# 1-Schematic_EMWAVER_V1_0_1.net
KiCad netlist of a schematic drawn in EasyEDA
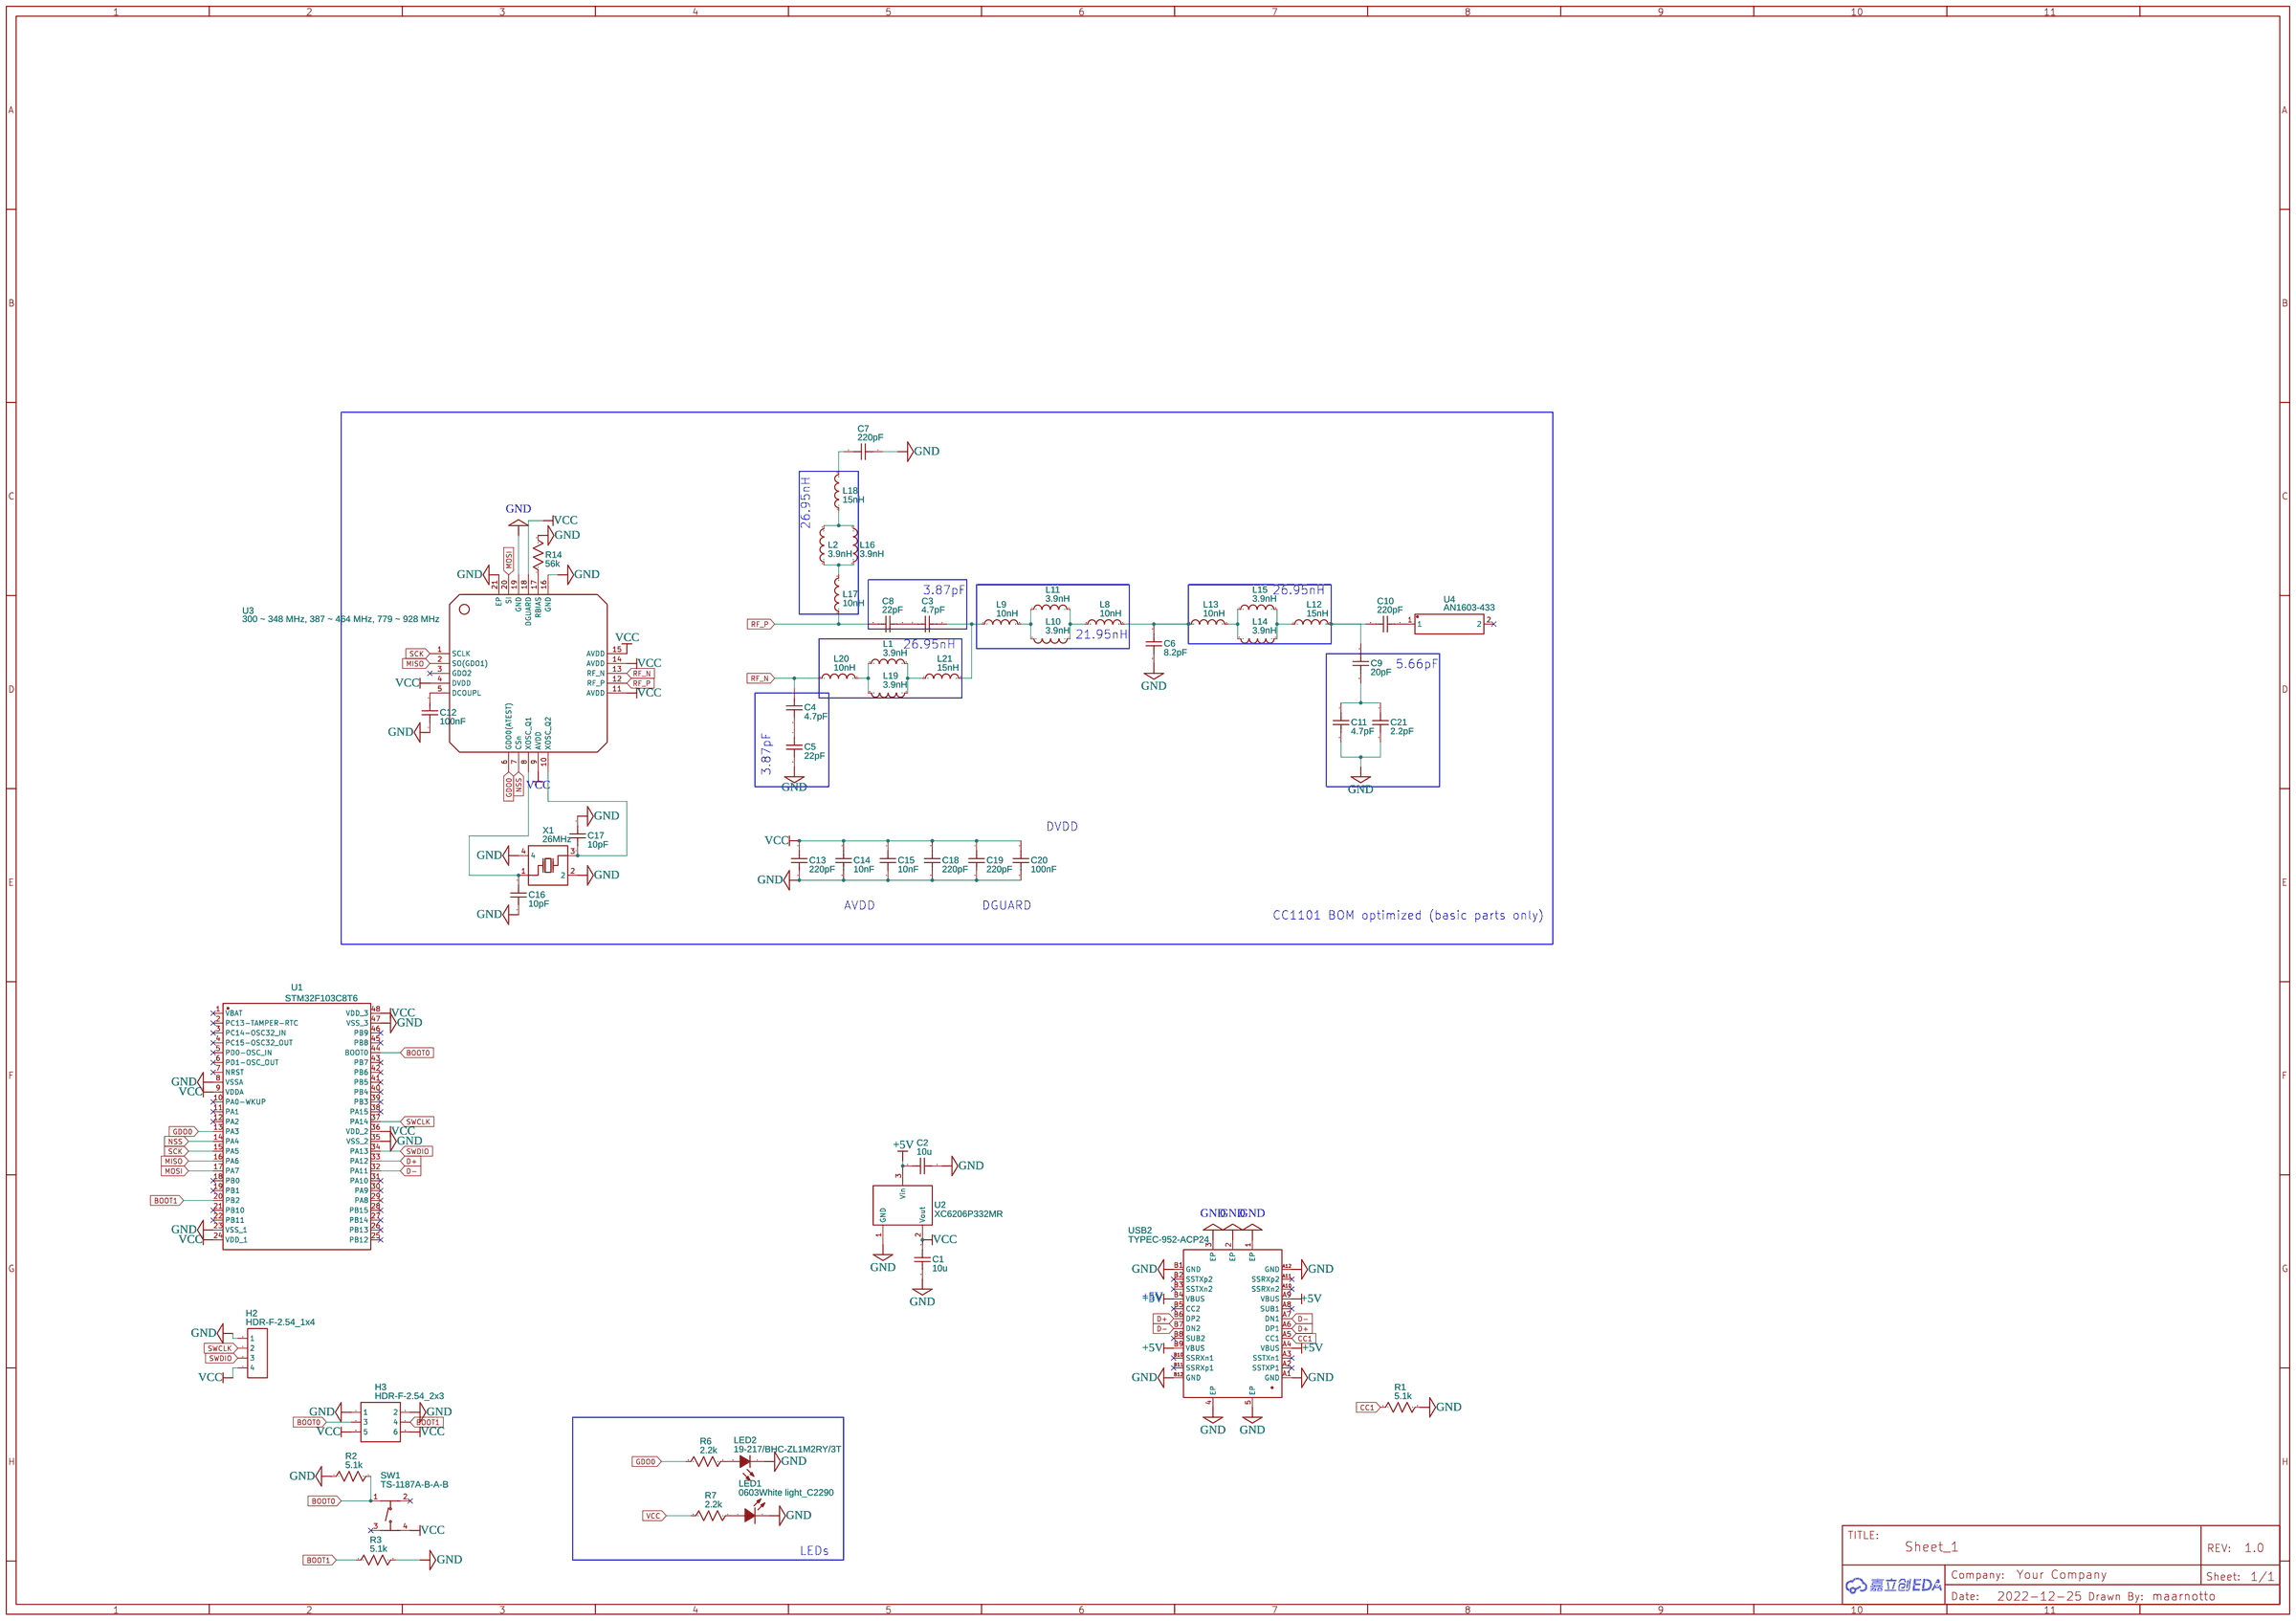
[diagram p0: schematic sheet]

(export (version "E")
  (design (tool "Eeschema 10.0.6"))
  (components
    (comp (ref "C1") (value "10u") (libsource (lib "") (part "C_0603_US_1")))
    (comp (ref "C2") (value "10u") (libsource (lib "") (part "C_0603_US")))
    (comp (ref "C3") (value "4.7pF") (libsource (lib "") (part "C_0402_US_1")))
    (comp (ref "C4") (value "4.7pF") (libsource (lib "") (part "C_0402_US")))
    (comp (ref "C5") (value "22pF") (libsource (lib "") (part "C_0402_US")))
    (comp (ref "C6") (value "8.2pF") (libsource (lib "") (part "C_0603_US_1")))
    (comp (ref "C7") (value "220pF") (libsource (lib "") (part "C_0402_US_1")))
    (comp (ref "C8") (value "22pF") (libsource (lib "") (part "C_0402_US_1")))
    (comp (ref "C9") (value "20pF") (libsource (lib "") (part "C_0402_US")))
    (comp (ref "C10") (value "220pF") (libsource (lib "") (part "C_0402_US_1")))
    (comp (ref "C11") (value "4.7pF") (libsource (lib "") (part "C_0402_US")))
    (comp (ref "C12") (value "100nF") (libsource (lib "") (part "C_0402_US")))
    (comp (ref "C13") (value "220pF") (libsource (lib "") (part "C_0402_US")))
    (comp (ref "C14") (value "10nF") (libsource (lib "") (part "C_0402_US")))
    (comp (ref "C15") (value "10nF") (libsource (lib "") (part "C_0402_US")))
    (comp (ref "C16") (value "10pF") (libsource (lib "") (part "C_0402_US")))
    (comp (ref "C17") (value "10pF") (libsource (lib "") (part "C_0402_US_2")))
    (comp (ref "C18") (value "220pF") (libsource (lib "") (part "C_0402_US")))
    (comp (ref "C19") (value "220pF") (libsource (lib "") (part "C_0402_US")))
    (comp (ref "C20") (value "100nF") (libsource (lib "") (part "C_0402_US")))
    (comp (ref "C21") (value "2.2pF") (libsource (lib "") (part "C_0402_US")))
    (comp (ref "H2")
      (value "HDR-F-2.54_1x4")
      (fields (field (name "BOM_Supplier Part") "C225501"))
      (libsource (lib "") (part "HDR-F-2.54_1x4"))
    )
    (comp (ref "H3")
      (value "HDR-F-2.54_2x3")
      (fields (field (name "BOM_Supplier Part") "C65114"))
      (libsource (lib "") (part "HDR-F-2.54_2x3"))
    )
    (comp (ref "L1")
      (value "3.9nH")
      (fields (field (name "BOM_Supplier Part") "C14033"))
      (libsource (lib "") (part "L0402_US_1"))
    )
    (comp (ref "L2")
      (value "3.9nH")
      (fields (field (name "BOM_Supplier Part") "C14033"))
      (libsource (lib "") (part "L0402_US_3"))
    )
    (comp (ref "L8")
      (value "10nH")
      (fields (field (name "BOM_Supplier Part") "C27147"))
      (libsource (lib "") (part "L0402_US"))
    )
    (comp (ref "L9")
      (value "10nH")
      (fields (field (name "BOM_Supplier Part") "C27147"))
      (libsource (lib "") (part "L0402_US_1"))
    )
    (comp (ref "L10")
      (value "3.9nH")
      (fields (field (name "BOM_Supplier Part") "C14033"))
      (libsource (lib "") (part "L0402_US_4"))
    )
    (comp (ref "L11")
      (value "3.9nH")
      (fields (field (name "BOM_Supplier Part") "C14033"))
      (libsource (lib "") (part "L0402_US"))
    )
    (comp (ref "L12")
      (value "15nH")
      (fields (field (name "BOM_Supplier Part") "C27143"))
      (libsource (lib "") (part "L0402_US"))
    )
    (comp (ref "L13")
      (value "10nH")
      (fields (field (name "BOM_Supplier Part") "C27147"))
      (libsource (lib "") (part "L0402_US"))
    )
    (comp (ref "L14")
      (value "3.9nH")
      (fields (field (name "BOM_Supplier Part") "C14033"))
      (libsource (lib "") (part "L0402_US_4"))
    )
    (comp (ref "L15")
      (value "3.9nH")
      (fields (field (name "BOM_Supplier Part") "C14033"))
      (libsource (lib "") (part "L0402_US"))
    )
    (comp (ref "L16")
      (value "3.9nH")
      (fields (field (name "BOM_Supplier Part") "C14033"))
      (libsource (lib "") (part "L0402_US_2"))
    )
    (comp (ref "L17")
      (value "10nH")
      (fields (field (name "BOM_Supplier Part") "C27147"))
      (libsource (lib "") (part "L0402_US_3"))
    )
    (comp (ref "L18")
      (value "15nH")
      (fields (field (name "BOM_Supplier Part") "C27143"))
      (libsource (lib "") (part "L0402_US_3"))
    )
    (comp (ref "L19")
      (value "3.9nH")
      (fields (field (name "BOM_Supplier Part") "C14033"))
      (libsource (lib "") (part "L0402_US_5"))
    )
    (comp (ref "L20")
      (value "10nH")
      (fields (field (name "BOM_Supplier Part") "C27147"))
      (libsource (lib "") (part "L0402_US_1"))
    )
    (comp (ref "L21")
      (value "15nH")
      (fields (field (name "BOM_Supplier Part") "C27143"))
      (libsource (lib "") (part "L0402_US_1"))
    )
    (comp (ref "LED1")
      (value "0603White light_C2290")
      (fields (field (name "BOM_Manufacturer Part") "KT-0603白灯") (field (name "BOM_Supplier Part") "C2290"))
      (libsource (lib "") (part "0603White light_C2290"))
    )
    (comp (ref "LED2")
      (value "19-217/BHC-ZL1M2RY/3T")
      (fields (field (name "BOM_Supplier Part") "C72041"))
      (libsource (lib "") (part "19-217/BHC-ZL1M2RY/3T"))
    )
    (comp (ref "R1") (value "5.1k") (libsource (lib "") (part "R_0603_US")))
    (comp (ref "R2") (value "5.1k") (libsource (lib "") (part "R_0603_US")))
    (comp (ref "R3") (value "5.1k") (libsource (lib "") (part "R_0603_US")))
    (comp (ref "R6") (value "2.2k") (libsource (lib "") (part "R_0603_US")))
    (comp (ref "R7") (value "2.2k") (libsource (lib "") (part "R_0603_US")))
    (comp (ref "R14") (value "56k") (libsource (lib "") (part "R_0402_US")))
    (comp (ref "SW1")
      (value "TS-1187A-B-A-B")
      (fields (field (name "BOM_Supplier Part") "C318884"))
      (libsource (lib "") (part "TS-1187A-B-A-B"))
    )
    (comp (ref "U1")
      (value "STM32F103C8T6")
      (fields (field (name "BOM_Supplier Part") "C8734"))
      (libsource (lib "") (part "STM32F103C8T6"))
    )
    (comp (ref "U2")
      (value "XC6206P332MR")
      (fields (field (name "BOM_Supplier Part") "C5446"))
      (libsource (lib "") (part "XC6206P332MR"))
    )
    (comp (ref "U3")
      (value "300 ~ 348 MHz, 387 ~ 464 MHz, 779 ~ 928 MHz")
      (fields (field (name "BOM_Manufacturer Part") "CC1101RGPR") (field (name "BOM_Supplier Part") "C29953"))
      (libsource (lib "") (part "CC1101RGPR"))
    )
    (comp (ref "U4")
      (value "AN1603-433")
      (fields (field (name "BOM_Supplier Part") "C122806"))
      (libsource (lib "") (part "AN1603-433"))
    )
    (comp (ref "USB2")
      (value "TYPEC-952-ACP24")
      (fields (field (name "BOM_Supplier Part") "C2840398"))
      (libsource (lib "") (part "TYPEC-952-ACP24"))
    )
    (comp (ref "X1")
      (value "26MHz")
      (fields
        (field (name "BOM_Manufacturer Part") "3S26000333")
        (field (name "BOM_Supplier Part") "C431163")
      )
      (libsource (lib "") (part "3S26000333"))
    )
  )
  (nets
    (net (code "1") (name "+5V") (class "Default")
      (node (ref "C2") (pin "2") (pinfunction "2_2") (pintype "unspecified"))
      (node (ref "U2") (pin "3") (pinfunction "Vin_3") (pintype "unspecified"))
      (node (ref "USB2") (pin "A4") (pinfunction "VBUS_A4") (pintype "unspecified"))
      (node (ref "USB2") (pin "A9") (pinfunction "VBUS_A9") (pintype "unspecified"))
      (node (ref "USB2") (pin "B4") (pinfunction "VBUS_B4") (pintype "unspecified"))
      (node (ref "USB2") (pin "B9") (pinfunction "VBUS_B9") (pintype "unspecified"))
    )
    (net (code "2") (name "BOOT0") (class "Default")
      (node (ref "H3") (pin "3") (pinfunction "3_3") (pintype "input"))
      (node (ref "R2") (pin "2") (pinfunction "2_2") (pintype "unspecified"))
      (node (ref "SW1") (pin "1") (pinfunction "A_1") (pintype "unspecified"))
      (node (ref "U1") (pin "44") (pinfunction "BOOT0_44") (pintype "unspecified"))
    )
    (net (code "3") (name "BOOT1") (class "Default")
      (node (ref "H3") (pin "4") (pinfunction "4_4") (pintype "input"))
      (node (ref "R3") (pin "1") (pinfunction "1_1") (pintype "unspecified"))
      (node (ref "U1") (pin "20") (pinfunction "PB2_20") (pintype "unspecified"))
    )
    (net (code "4") (name "CC1") (class "Default")
      (node (ref "R1") (pin "1") (pinfunction "1_1") (pintype "unspecified"))
      (node (ref "USB2") (pin "A5") (pinfunction "CC1_A5") (pintype "unspecified"))
    )
    (net (code "5") (name "D+") (class "Default")
      (node (ref "U1") (pin "33") (pinfunction "PA12_33") (pintype "unspecified"))
      (node (ref "USB2") (pin "A6") (pinfunction "DP1_A6") (pintype "unspecified"))
      (node (ref "USB2") (pin "B6") (pinfunction "DP2_B6") (pintype "unspecified"))
    )
    (net (code "6") (name "D-") (class "Default")
      (node (ref "U1") (pin "32") (pinfunction "PA11_32") (pintype "unspecified"))
      (node (ref "USB2") (pin "A7") (pinfunction "DN1_A7") (pintype "unspecified"))
      (node (ref "USB2") (pin "B7") (pinfunction "DN2_B7") (pintype "unspecified"))
    )
    (net (code "7") (name "GDO0") (class "Default")
      (node (ref "R6") (pin "1") (pinfunction "1_1") (pintype "unspecified"))
      (node (ref "U1") (pin "13") (pinfunction "PA3_13") (pintype "unspecified"))
      (node (ref "U3") (pin "6") (pinfunction "GDO0(ATEST)_6") (pintype "unspecified"))
    )
    (net (code "8") (name "GND") (class "Default")
      (node (ref "C1") (pin "2") (pinfunction "2_2") (pintype "unspecified"))
      (node (ref "C11") (pin "2") (pinfunction "2_2") (pintype "unspecified"))
      (node (ref "C12") (pin "2") (pinfunction "2_2") (pintype "unspecified"))
      (node (ref "C13") (pin "2") (pinfunction "2_2") (pintype "unspecified"))
      (node (ref "C14") (pin "2") (pinfunction "2_2") (pintype "unspecified"))
      (node (ref "C15") (pin "2") (pinfunction "2_2") (pintype "unspecified"))
      (node (ref "C16") (pin "2") (pinfunction "2_2") (pintype "unspecified"))
      (node (ref "C17") (pin "2") (pinfunction "2_2") (pintype "unspecified"))
      (node (ref "C18") (pin "2") (pinfunction "2_2") (pintype "unspecified"))
      (node (ref "C19") (pin "2") (pinfunction "2_2") (pintype "unspecified"))
      (node (ref "C2") (pin "1") (pinfunction "1_1") (pintype "unspecified"))
      (node (ref "C20") (pin "2") (pinfunction "2_2") (pintype "unspecified"))
      (node (ref "C21") (pin "2") (pinfunction "2_2") (pintype "unspecified"))
      (node (ref "C5") (pin "2") (pinfunction "2_2") (pintype "unspecified"))
      (node (ref "C6") (pin "2") (pinfunction "2_2") (pintype "unspecified"))
      (node (ref "C7") (pin "1") (pinfunction "1_1") (pintype "unspecified"))
      (node (ref "H2") (pin "1") (pinfunction "1_1") (pintype "unspecified"))
      (node (ref "H3") (pin "1") (pinfunction "1_1") (pintype "input"))
      (node (ref "H3") (pin "2") (pinfunction "2_2") (pintype "input"))
      (node (ref "LED1") (pin "2") (pinfunction "K_2") (pintype "unspecified"))
      (node (ref "LED2") (pin "1") (pinfunction "C_1") (pintype "input"))
      (node (ref "R1") (pin "2") (pinfunction "2_2") (pintype "unspecified"))
      (node (ref "R14") (pin "2") (pinfunction "2_2") (pintype "unspecified"))
      (node (ref "R2") (pin "1") (pinfunction "1_1") (pintype "unspecified"))
      (node (ref "R3") (pin "2") (pinfunction "2_2") (pintype "unspecified"))
      (node (ref "U1") (pin "23") (pinfunction "VSS_1_23") (pintype "unspecified"))
      (node (ref "U1") (pin "35") (pinfunction "VSS_2_35") (pintype "unspecified"))
      (node (ref "U1") (pin "47") (pinfunction "VSS_3_47") (pintype "unspecified"))
      (node (ref "U1") (pin "8") (pinfunction "VSSA_8") (pintype "unspecified"))
      (node (ref "U2") (pin "1") (pinfunction "GND_1") (pintype "unspecified"))
      (node (ref "U3") (pin "16") (pinfunction "GND_16") (pintype "unspecified"))
      (node (ref "U3") (pin "19") (pinfunction "GND_19") (pintype "unspecified"))
      (node (ref "U3") (pin "21") (pinfunction "EP_21") (pintype "unspecified"))
      (node (ref "USB2") (pin "1") (pinfunction "EP_1") (pintype "unspecified"))
      (node (ref "USB2") (pin "2") (pinfunction "EP_2") (pintype "unspecified"))
      (node (ref "USB2") (pin "3") (pinfunction "EP_3") (pintype "unspecified"))
      (node (ref "USB2") (pin "4") (pinfunction "EP_4") (pintype "unspecified"))
      (node (ref "USB2") (pin "5") (pinfunction "EP_5") (pintype "unspecified"))
      (node (ref "USB2") (pin "A1") (pinfunction "GND_A1") (pintype "unspecified"))
      (node (ref "USB2") (pin "A12") (pinfunction "GND_A12") (pintype "unspecified"))
      (node (ref "USB2") (pin "B1") (pinfunction "GND_B1") (pintype "unspecified"))
      (node (ref "USB2") (pin "B12") (pinfunction "GND_B12") (pintype "unspecified"))
      (node (ref "X1") (pin "2") (pinfunction "2_2") (pintype "unspecified"))
      (node (ref "X1") (pin "4") (pinfunction "4_4") (pintype "unspecified"))
    )
    (net (code "9") (name "MISO") (class "Default")
      (node (ref "U1") (pin "16") (pinfunction "PA6_16") (pintype "unspecified"))
      (node (ref "U3") (pin "2") (pinfunction "SO(GDO1)_2") (pintype "unspecified"))
    )
    (net (code "10") (name "MOSI") (class "Default")
      (node (ref "U1") (pin "17") (pinfunction "PA7_17") (pintype "unspecified"))
      (node (ref "U3") (pin "20") (pinfunction "SI_20") (pintype "unspecified"))
    )
    (net (code "11") (name "NSS") (class "Default")
      (node (ref "U1") (pin "14") (pinfunction "PA4_14") (pintype "unspecified"))
      (node (ref "U3") (pin "7") (pinfunction "CSn_7") (pintype "unspecified"))
    )
    (net (code "12") (name "Net-(C3-Pad1)") (class "Default")
      (node (ref "C3") (pin "1") (pinfunction "1_1") (pintype "unspecified"))
      (node (ref "L21") (pin "2") (pinfunction "2_2") (pintype "unspecified"))
      (node (ref "L9") (pin "1") (pinfunction "1_1") (pintype "unspecified"))
    )
    (net (code "13") (name "Net-(C3-Pad2)") (class "Default")
      (node (ref "C3") (pin "2") (pinfunction "2_2") (pintype "unspecified"))
      (node (ref "C8") (pin "1") (pinfunction "1_1") (pintype "unspecified"))
    )
    (net (code "14") (name "Net-(C4-Pad2)") (class "Default")
      (node (ref "C4") (pin "2") (pinfunction "2_2") (pintype "unspecified"))
      (node (ref "C5") (pin "1") (pinfunction "1_1") (pintype "unspecified"))
    )
    (net (code "15") (name "Net-(C6-Pad1)") (class "Default")
      (node (ref "C6") (pin "1") (pinfunction "1_1") (pintype "unspecified"))
      (node (ref "L13") (pin "1") (pinfunction "1_1") (pintype "unspecified"))
      (node (ref "L8") (pin "2") (pinfunction "2_2") (pintype "unspecified"))
    )
    (net (code "16") (name "Net-(C7-Pad2)") (class "Default")
      (node (ref "C7") (pin "2") (pinfunction "2_2") (pintype "unspecified"))
      (node (ref "L18") (pin "2") (pinfunction "2_2") (pintype "unspecified"))
    )
    (net (code "17") (name "Net-(C10-Pad1)") (class "Default")
      (node (ref "C10") (pin "1") (pinfunction "1_1") (pintype "unspecified"))
      (node (ref "U4") (pin "1") (pinfunction "1_1") (pintype "unspecified"))
    )
    (net (code "18") (name "Net-(C10-Pad2)") (class "Default")
      (node (ref "C10") (pin "2") (pinfunction "2_2") (pintype "unspecified"))
      (node (ref "C9") (pin "1") (pinfunction "1_1") (pintype "unspecified"))
      (node (ref "L12") (pin "2") (pinfunction "2_2") (pintype "unspecified"))
    )
    (net (code "19") (name "Net-(C11-Pad1)") (class "Default")
      (node (ref "C11") (pin "1") (pinfunction "1_1") (pintype "unspecified"))
      (node (ref "C21") (pin "1") (pinfunction "1_1") (pintype "unspecified"))
      (node (ref "C9") (pin "2") (pinfunction "2_2") (pintype "unspecified"))
    )
    (net (code "20") (name "Net-(L1-Pad1)") (class "Default")
      (node (ref "L1") (pin "1") (pinfunction "1_1") (pintype "unspecified"))
      (node (ref "L19") (pin "2") (pinfunction "2_2") (pintype "unspecified"))
      (node (ref "L20") (pin "2") (pinfunction "2_2") (pintype "unspecified"))
    )
    (net (code "21") (name "Net-(L1-Pad2)") (class "Default")
      (node (ref "L1") (pin "2") (pinfunction "2_2") (pintype "unspecified"))
      (node (ref "L19") (pin "1") (pinfunction "1_1") (pintype "unspecified"))
      (node (ref "L21") (pin "1") (pinfunction "1_1") (pintype "unspecified"))
    )
    (net (code "22") (name "Net-(L10-Pad1)") (class "Default")
      (node (ref "L10") (pin "1") (pinfunction "1_1") (pintype "unspecified"))
      (node (ref "L11") (pin "2") (pinfunction "2_2") (pintype "unspecified"))
      (node (ref "L8") (pin "1") (pinfunction "1_1") (pintype "unspecified"))
    )
    (net (code "23") (name "Net-(L10-Pad2)") (class "Default")
      (node (ref "L10") (pin "2") (pinfunction "2_2") (pintype "unspecified"))
      (node (ref "L11") (pin "1") (pinfunction "1_1") (pintype "unspecified"))
      (node (ref "L9") (pin "2") (pinfunction "2_2") (pintype "unspecified"))
    )
    (net (code "24") (name "Net-(L12-Pad1)") (class "Default")
      (node (ref "L12") (pin "1") (pinfunction "1_1") (pintype "unspecified"))
      (node (ref "L14") (pin "1") (pinfunction "1_1") (pintype "unspecified"))
      (node (ref "L15") (pin "2") (pinfunction "2_2") (pintype "unspecified"))
    )
    (net (code "25") (name "Net-(L13-Pad2)") (class "Default")
      (node (ref "L13") (pin "2") (pinfunction "2_2") (pintype "unspecified"))
      (node (ref "L14") (pin "2") (pinfunction "2_2") (pintype "unspecified"))
      (node (ref "L15") (pin "1") (pinfunction "1_1") (pintype "unspecified"))
    )
    (net (code "26") (name "Net-(L16-Pad1)") (class "Default")
      (node (ref "L16") (pin "1") (pinfunction "1_1") (pintype "unspecified"))
      (node (ref "L18") (pin "1") (pinfunction "1_1") (pintype "unspecified"))
      (node (ref "L2") (pin "2") (pinfunction "2_2") (pintype "unspecified"))
    )
    (net (code "27") (name "Net-(L16-Pad2)") (class "Default")
      (node (ref "L16") (pin "2") (pinfunction "2_2") (pintype "unspecified"))
      (node (ref "L17") (pin "2") (pinfunction "2_2") (pintype "unspecified"))
      (node (ref "L2") (pin "1") (pinfunction "1_1") (pintype "unspecified"))
    )
    (net (code "28") (name "Net-(LED1-A)") (class "Default")
      (node (ref "LED1") (pin "1") (pinfunction "A_1") (pintype "unspecified"))
      (node (ref "R7") (pin "2") (pinfunction "2_2") (pintype "unspecified"))
    )
    (net (code "29") (name "Net-(LED2-A)") (class "Default")
      (node (ref "LED2") (pin "2") (pinfunction "A_2") (pintype "input"))
      (node (ref "R6") (pin "2") (pinfunction "2_2") (pintype "unspecified"))
    )
    (net (code "30") (name "Net-(U3-DCOUPL)") (class "Default")
      (node (ref "C12") (pin "1") (pinfunction "1_1") (pintype "unspecified"))
      (node (ref "U3") (pin "5") (pinfunction "DCOUPL_5") (pintype "unspecified"))
    )
    (net (code "31") (name "Net-(U3-RBIAS)") (class "Default")
      (node (ref "R14") (pin "1") (pinfunction "1_1") (pintype "unspecified"))
      (node (ref "U3") (pin "17") (pinfunction "RBIAS_17") (pintype "unspecified"))
    )
    (net (code "32") (name "Net-(U3-XOSC_Q1)") (class "Default")
      (node (ref "C16") (pin "1") (pinfunction "1_1") (pintype "unspecified"))
      (node (ref "U3") (pin "8") (pinfunction "XOSC_Q1_8") (pintype "unspecified"))
      (node (ref "X1") (pin "1") (pinfunction "OSC1_1") (pintype "unspecified"))
    )
    (net (code "33") (name "Net-(U3-XOSC_Q2)") (class "Default")
      (node (ref "C17") (pin "1") (pinfunction "1_1") (pintype "unspecified"))
      (node (ref "U3") (pin "10") (pinfunction "XOSC_Q2_10") (pintype "unspecified"))
      (node (ref "X1") (pin "3") (pinfunction "OSC2_3") (pintype "unspecified"))
    )
    (net (code "34") (name "RF_N") (class "Default")
      (node (ref "C4") (pin "1") (pinfunction "1_1") (pintype "unspecified"))
      (node (ref "L20") (pin "1") (pinfunction "1_1") (pintype "unspecified"))
      (node (ref "U3") (pin "13") (pinfunction "RF_N_13") (pintype "unspecified"))
    )
    (net (code "35") (name "RF_P") (class "Default")
      (node (ref "C8") (pin "2") (pinfunction "2_2") (pintype "unspecified"))
      (node (ref "L17") (pin "1") (pinfunction "1_1") (pintype "unspecified"))
      (node (ref "U3") (pin "12") (pinfunction "RF_P_12") (pintype "unspecified"))
    )
    (net (code "36") (name "SCK") (class "Default")
      (node (ref "U1") (pin "15") (pinfunction "PA5_15") (pintype "unspecified"))
      (node (ref "U3") (pin "1") (pinfunction "SCLK_1") (pintype "unspecified"))
    )
    (net (code "37") (name "SWCLK") (class "Default")
      (node (ref "H2") (pin "2") (pinfunction "2_2") (pintype "unspecified"))
      (node (ref "U1") (pin "37") (pinfunction "PA14_37") (pintype "unspecified"))
    )
    (net (code "38") (name "SWDIO") (class "Default")
      (node (ref "H2") (pin "3") (pinfunction "3_3") (pintype "unspecified"))
      (node (ref "U1") (pin "34") (pinfunction "PA13_34") (pintype "unspecified"))
    )
    (net (code "39") (name "VCC") (class "Default")
      (node (ref "C1") (pin "1") (pinfunction "1_1") (pintype "unspecified"))
      (node (ref "C13") (pin "1") (pinfunction "1_1") (pintype "unspecified"))
      (node (ref "C14") (pin "1") (pinfunction "1_1") (pintype "unspecified"))
      (node (ref "C15") (pin "1") (pinfunction "1_1") (pintype "unspecified"))
      (node (ref "C18") (pin "1") (pinfunction "1_1") (pintype "unspecified"))
      (node (ref "C19") (pin "1") (pinfunction "1_1") (pintype "unspecified"))
      (node (ref "C20") (pin "1") (pinfunction "1_1") (pintype "unspecified"))
      (node (ref "H2") (pin "4") (pinfunction "4_4") (pintype "unspecified"))
      (node (ref "H3") (pin "5") (pinfunction "5_5") (pintype "input"))
      (node (ref "H3") (pin "6") (pinfunction "6_6") (pintype "input"))
      (node (ref "R7") (pin "1") (pinfunction "1_1") (pintype "unspecified"))
      (node (ref "SW1") (pin "4") (pinfunction "D_4") (pintype "unspecified"))
      (node (ref "U1") (pin "24") (pinfunction "VDD_1_24") (pintype "unspecified"))
      (node (ref "U1") (pin "36") (pinfunction "VDD_2_36") (pintype "unspecified"))
      (node (ref "U1") (pin "48") (pinfunction "VDD_3_48") (pintype "unspecified"))
      (node (ref "U1") (pin "9") (pinfunction "VDDA_9") (pintype "unspecified"))
      (node (ref "U2") (pin "2") (pinfunction "Vout_2") (pintype "unspecified"))
      (node (ref "U3") (pin "11") (pinfunction "AVDD_11") (pintype "unspecified"))
      (node (ref "U3") (pin "14") (pinfunction "AVDD_14") (pintype "unspecified"))
      (node (ref "U3") (pin "15") (pinfunction "AVDD_15") (pintype "unspecified"))
      (node (ref "U3") (pin "18") (pinfunction "DGUARD_18") (pintype "unspecified"))
      (node (ref "U3") (pin "4") (pinfunction "DVDD_4") (pintype "unspecified"))
      (node (ref "U3") (pin "9") (pinfunction "AVDD_9") (pintype "unspecified"))
    )
    (net (code "40") (name "unconnected-(SW1-B-Pad2)") (class "Default")
      (node (ref "SW1") (pin "2") (pinfunction "B_2") (pintype "unspecified+no_connect"))
    )
    (net (code "41") (name "unconnected-(SW1-C-Pad3)") (class "Default")
      (node (ref "SW1") (pin "3") (pinfunction "C_3") (pintype "unspecified+no_connect"))
    )
    (net (code "42") (name "unconnected-(U1-NRST-Pad7)") (class "Default")
      (node (ref "U1") (pin "7") (pinfunction "NRST_7") (pintype "unspecified+no_connect"))
    )
    (net (code "43") (name "unconnected-(U1-PA0-WKUP-Pad10)") (class "Default")
      (node (ref "U1") (pin "10") (pinfunction "PA0-WKUP_10") (pintype "unspecified+no_connect"))
    )
    (net (code "44") (name "unconnected-(U1-PA1-Pad11)") (class "Default")
      (node (ref "U1") (pin "11") (pinfunction "PA1_11") (pintype "unspecified+no_connect"))
    )
    (net (code "45") (name "unconnected-(U1-PA2-Pad12)") (class "Default")
      (node (ref "U1") (pin "12") (pinfunction "PA2_12") (pintype "unspecified+no_connect"))
    )
    (net (code "46") (name "unconnected-(U1-PA8-Pad29)") (class "Default")
      (node (ref "U1") (pin "29") (pinfunction "PA8_29") (pintype "unspecified+no_connect"))
    )
    (net (code "47") (name "unconnected-(U1-PA9-Pad30)") (class "Default")
      (node (ref "U1") (pin "30") (pinfunction "PA9_30") (pintype "unspecified+no_connect"))
    )
    (net (code "48") (name "unconnected-(U1-PA10-Pad31)") (class "Default")
      (node (ref "U1") (pin "31") (pinfunction "PA10_31") (pintype "unspecified+no_connect"))
    )
    (net (code "49") (name "unconnected-(U1-PA15-Pad38)") (class "Default")
      (node (ref "U1") (pin "38") (pinfunction "PA15_38") (pintype "unspecified+no_connect"))
    )
    (net (code "50") (name "unconnected-(U1-PB0-Pad18)") (class "Default")
      (node (ref "U1") (pin "18") (pinfunction "PB0_18") (pintype "unspecified+no_connect"))
    )
    (net (code "51") (name "unconnected-(U1-PB1-Pad19)") (class "Default")
      (node (ref "U1") (pin "19") (pinfunction "PB1_19") (pintype "unspecified+no_connect"))
    )
    (net (code "52") (name "unconnected-(U1-PB3-Pad39)") (class "Default")
      (node (ref "U1") (pin "39") (pinfunction "PB3_39") (pintype "unspecified+no_connect"))
    )
    (net (code "53") (name "unconnected-(U1-PB4-Pad40)") (class "Default")
      (node (ref "U1") (pin "40") (pinfunction "PB4_40") (pintype "unspecified+no_connect"))
    )
    (net (code "54") (name "unconnected-(U1-PB5-Pad41)") (class "Default")
      (node (ref "U1") (pin "41") (pinfunction "PB5_41") (pintype "unspecified+no_connect"))
    )
    (net (code "55") (name "unconnected-(U1-PB6-Pad42)") (class "Default")
      (node (ref "U1") (pin "42") (pinfunction "PB6_42") (pintype "unspecified+no_connect"))
    )
    (net (code "56") (name "unconnected-(U1-PB7-Pad43)") (class "Default")
      (node (ref "U1") (pin "43") (pinfunction "PB7_43") (pintype "unspecified+no_connect"))
    )
    (net (code "57") (name "unconnected-(U1-PB8-Pad45)") (class "Default")
      (node (ref "U1") (pin "45") (pinfunction "PB8_45") (pintype "unspecified+no_connect"))
    )
    (net (code "58") (name "unconnected-(U1-PB9-Pad46)") (class "Default")
      (node (ref "U1") (pin "46") (pinfunction "PB9_46") (pintype "unspecified+no_connect"))
    )
    (net (code "59") (name "unconnected-(U1-PB10-Pad21)") (class "Default")
      (node (ref "U1") (pin "21") (pinfunction "PB10_21") (pintype "unspecified+no_connect"))
    )
    (net (code "60") (name "unconnected-(U1-PB11-Pad22)") (class "Default")
      (node (ref "U1") (pin "22") (pinfunction "PB11_22") (pintype "unspecified+no_connect"))
    )
    (net (code "61") (name "unconnected-(U1-PB12-Pad25)") (class "Default")
      (node (ref "U1") (pin "25") (pinfunction "PB12_25") (pintype "unspecified+no_connect"))
    )
    (net (code "62") (name "unconnected-(U1-PB13-Pad26)") (class "Default")
      (node (ref "U1") (pin "26") (pinfunction "PB13_26") (pintype "unspecified+no_connect"))
    )
    (net (code "63") (name "unconnected-(U1-PB14-Pad27)") (class "Default")
      (node (ref "U1") (pin "27") (pinfunction "PB14_27") (pintype "unspecified+no_connect"))
    )
    (net (code "64") (name "unconnected-(U1-PB15-Pad28)") (class "Default")
      (node (ref "U1") (pin "28") (pinfunction "PB15_28") (pintype "unspecified+no_connect"))
    )
    (net (code "65") (name "unconnected-(U1-PC13-TAMPER-RTC-Pad2)") (class "Default")
      (node (ref "U1") (pin "2") (pinfunction "PC13-TAMPER-RTC_2") (pintype "unspecified+no_connect"))
    )
    (net (code "66") (name "unconnected-(U1-PC14-OSC32_IN-Pad3)") (class "Default")
      (node (ref "U1") (pin "3") (pinfunction "PC14-OSC32_IN_3") (pintype "unspecified+no_connect"))
    )
    (net (code "67") (name "unconnected-(U1-PC15-OSC32_OUT-Pad4)") (class "Default")
      (node (ref "U1") (pin "4") (pinfunction "PC15-OSC32_OUT_4") (pintype "unspecified+no_connect"))
    )
    (net (code "68") (name "unconnected-(U1-PD0-OSC_IN-Pad5)") (class "Default")
      (node (ref "U1") (pin "5") (pinfunction "PD0-OSC_IN_5") (pintype "unspecified+no_connect"))
    )
    (net (code "69") (name "unconnected-(U1-PD1-OSC_OUT-Pad6)") (class "Default")
      (node (ref "U1") (pin "6") (pinfunction "PD1-OSC_OUT_6") (pintype "unspecified+no_connect"))
    )
    (net (code "70") (name "unconnected-(U1-VBAT-Pad1)") (class "Default")
      (node (ref "U1") (pin "1") (pinfunction "VBAT_1") (pintype "unspecified+no_connect"))
    )
    (net (code "71") (name "unconnected-(U3-GDO2-Pad3)") (class "Default")
      (node (ref "U3") (pin "3") (pinfunction "GDO2_3") (pintype "unspecified+no_connect"))
    )
    (net (code "72") (name "unconnected-(U4-Pad2)") (class "Default")
      (node (ref "U4") (pin "2") (pinfunction "2_2") (pintype "unspecified+no_connect"))
    )
    (net (code "73") (name "unconnected-(USB2-CC2-PadB5)") (class "Default")
      (node (ref "USB2") (pin "B5") (pinfunction "CC2_B5") (pintype "unspecified+no_connect"))
    )
    (net (code "74") (name "unconnected-(USB2-SSRXn1-PadB10)") (class "Default")
      (node (ref "USB2") (pin "B10") (pinfunction "SSRXn1_B10") (pintype "unspecified+no_connect"))
    )
    (net (code "75") (name "unconnected-(USB2-SSRXn2-PadA10)") (class "Default")
      (node (ref "USB2") (pin "A10") (pinfunction "SSRXn2_A10") (pintype "unspecified+no_connect"))
    )
    (net (code "76") (name "unconnected-(USB2-SSRXp1-PadB11)") (class "Default")
      (node (ref "USB2") (pin "B11") (pinfunction "SSRXp1_B11") (pintype "unspecified+no_connect"))
    )
    (net (code "77") (name "unconnected-(USB2-SSRXp2-PadA11)") (class "Default")
      (node (ref "USB2") (pin "A11") (pinfunction "SSRXp2_A11") (pintype "unspecified+no_connect"))
    )
    (net (code "78") (name "unconnected-(USB2-SSTXP1-PadA2)") (class "Default")
      (node (ref "USB2") (pin "A2") (pinfunction "SSTXP1_A2") (pintype "unspecified+no_connect"))
    )
    (net (code "79") (name "unconnected-(USB2-SSTXn1-PadA3)") (class "Default")
      (node (ref "USB2") (pin "A3") (pinfunction "SSTXn1_A3") (pintype "unspecified+no_connect"))
    )
    (net (code "80") (name "unconnected-(USB2-SSTXn2-PadB3)") (class "Default")
      (node (ref "USB2") (pin "B3") (pinfunction "SSTXn2_B3") (pintype "unspecified+no_connect"))
    )
    (net (code "81") (name "unconnected-(USB2-SSTXp2-PadB2)") (class "Default")
      (node (ref "USB2") (pin "B2") (pinfunction "SSTXp2_B2") (pintype "unspecified+no_connect"))
    )
    (net (code "82") (name "unconnected-(USB2-SUB1-PadA8)") (class "Default")
      (node (ref "USB2") (pin "A8") (pinfunction "SUB1_A8") (pintype "unspecified+no_connect"))
    )
    (net (code "83") (name "unconnected-(USB2-SUB2-PadB8)") (class "Default")
      (node (ref "USB2") (pin "B8") (pinfunction "SUB2_B8") (pintype "unspecified+no_connect"))
    )
  )
)
